# NotSoSmartWatch-BASIC-BOTTOM-version2.net
KiCad netlist of a schematic drawn in EAGLE
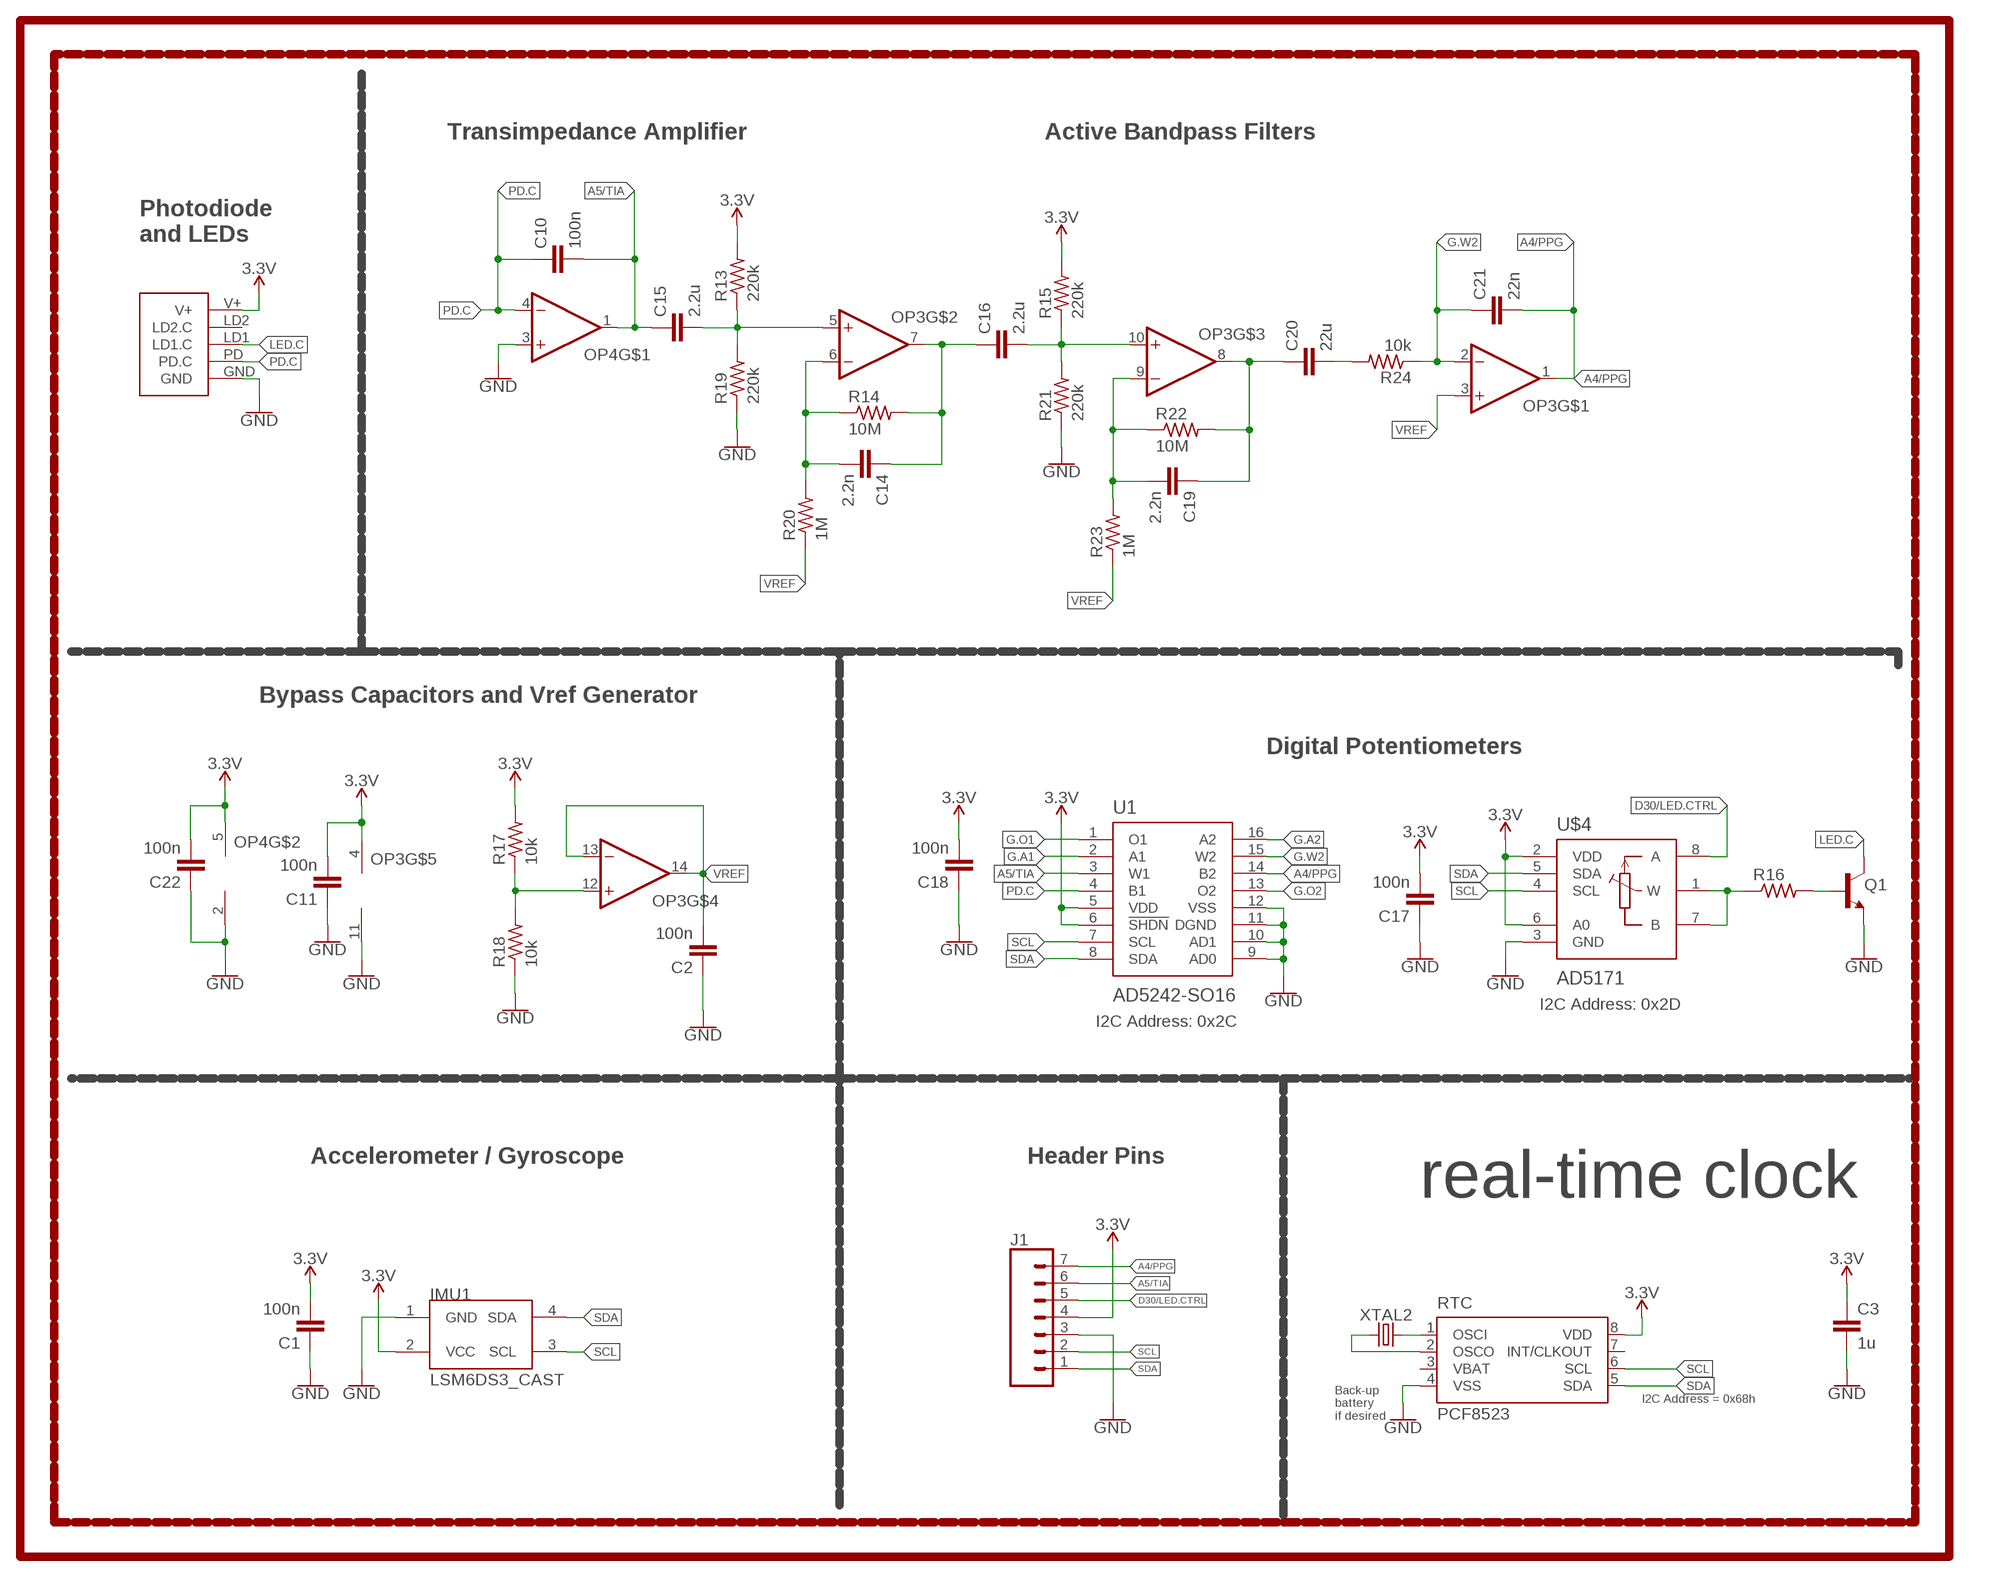
[diagram p0: schematic, sheet 1]

(export (version "E")
  (design (tool "Eeschema 10.0.6"))
  (components
    (comp (ref "C1")
      (value "100n")
      (footprint "eagle-import:C0603")
      (libsource (lib "eagle-import") (part "CAPACITOR0603"))
    )
    (comp (ref "C2")
      (value "100n")
      (footprint "eagle-import:C0603")
      (libsource (lib "eagle-import") (part "CAPACITOR0603"))
    )
    (comp (ref "C3")
      (value "1u")
      (footprint "eagle-import:C0603")
      (libsource (lib "eagle-import") (part "CAPACITOR0603"))
    )
    (comp (ref "C10")
      (value "100n")
      (footprint "eagle-import:C0603")
      (libsource (lib "eagle-import") (part "CAPACITOR0603"))
    )
    (comp (ref "C11")
      (value "100n")
      (footprint "eagle-import:C0603")
      (libsource (lib "eagle-import") (part "CAPACITOR0603"))
    )
    (comp (ref "C14")
      (value "2.2n")
      (footprint "eagle-import:C0603")
      (libsource (lib "eagle-import") (part "CAPACITOR0603"))
    )
    (comp (ref "C15")
      (value "2.2u")
      (footprint "eagle-import:C0603")
      (libsource (lib "eagle-import") (part "CAPACITOR0603"))
    )
    (comp (ref "C16")
      (value "2.2u")
      (footprint "eagle-import:C0603")
      (libsource (lib "eagle-import") (part "CAPACITOR0603"))
    )
    (comp (ref "C17")
      (value "100n")
      (footprint "eagle-import:C0603")
      (libsource (lib "eagle-import") (part "CAPACITOR0603"))
    )
    (comp (ref "C18")
      (value "100n")
      (footprint "eagle-import:C0603")
      (libsource (lib "eagle-import") (part "CAPACITOR0603"))
    )
    (comp (ref "C19")
      (value "2.2n")
      (footprint "eagle-import:C0603")
      (libsource (lib "eagle-import") (part "CAPACITOR0603"))
    )
    (comp (ref "C20")
      (value "22u")
      (footprint "eagle-import:C0603")
      (libsource (lib "eagle-import") (part "CAPACITOR0603"))
    )
    (comp (ref "C21")
      (value "22n")
      (footprint "eagle-import:C0603")
      (libsource (lib "eagle-import") (part "CAPACITOR0603"))
    )
    (comp (ref "C22")
      (value "100n")
      (footprint "eagle-import:C0603")
      (libsource (lib "eagle-import") (part "CAPACITOR0603"))
    )
    (comp (ref "IMU1")
      (value "LSM6DS3_CAST")
      (footprint "eagle-import:LSM6DS3_CAST")
      (libsource (lib "eagle-import") (part "LSM6DS3_CAST"))
    )
    (comp (ref "J1")
      (value "CONN_07-1.27MM")
      (footprint "eagle-import:1X07_1.27MM")
      (libsource (lib "eagle-import") (part "CONN_07-1.27MM"))
    )
    (comp (ref "OP3")
      (value "OP-QUAD-SO14")
      (footprint "eagle-import:SO14")
      (libsource (lib "eagle-import") (part "OP-QUAD-SO14"))
    )
    (comp (ref "OP4")
      (value "OP-SINGLEOT")
      (footprint "eagle-import:SOT23-5")
      (libsource (lib "eagle-import") (part "OP-SINGLEOT"))
    )
    (comp (ref "Q1")
      (value "NPN-GENERIC")
      (footprint "eagle-import:SOT23-3")
      (libsource (lib "eagle-import") (part "NPN-GENERIC"))
    )
    (comp (ref "R13")
      (value "220k")
      (footprint "eagle-import:R0603")
      (libsource (lib "eagle-import") (part "RESISTOR0603"))
    )
    (comp (ref "R14")
      (value "10M")
      (footprint "eagle-import:R0603")
      (libsource (lib "eagle-import") (part "RESISTOR0603"))
    )
    (comp (ref "R15")
      (value "220k")
      (footprint "eagle-import:R0603")
      (libsource (lib "eagle-import") (part "RESISTOR0603"))
    )
    (comp (ref "R16")
      (value "RESISTOR0603")
      (footprint "eagle-import:R0603")
      (libsource (lib "eagle-import") (part "RESISTOR0603"))
    )
    (comp (ref "R17")
      (value "10k")
      (footprint "eagle-import:R0402")
      (libsource (lib "eagle-import") (part "RESISTOR0402"))
    )
    (comp (ref "R18")
      (value "10k")
      (footprint "eagle-import:R0402")
      (libsource (lib "eagle-import") (part "RESISTOR0402"))
    )
    (comp (ref "R19")
      (value "220k")
      (footprint "eagle-import:R0603")
      (libsource (lib "eagle-import") (part "RESISTOR0603"))
    )
    (comp (ref "R20")
      (value "1M")
      (footprint "eagle-import:R0603")
      (libsource (lib "eagle-import") (part "RESISTOR0603"))
    )
    (comp (ref "R21")
      (value "220k")
      (footprint "eagle-import:R0603")
      (libsource (lib "eagle-import") (part "RESISTOR0603"))
    )
    (comp (ref "R22")
      (value "10M")
      (footprint "eagle-import:R0603")
      (libsource (lib "eagle-import") (part "RESISTOR0603"))
    )
    (comp (ref "R23")
      (value "1M")
      (footprint "eagle-import:R0603")
      (libsource (lib "eagle-import") (part "RESISTOR0603"))
    )
    (comp (ref "R24")
      (value "10k")
      (footprint "eagle-import:R0603")
      (libsource (lib "eagle-import") (part "RESISTOR0603"))
    )
    (comp (ref "RTC")
      (value "PCF8523")
      (footprint "eagle-import:SO8")
      (libsource (lib "eagle-import") (part "PCF8523"))
    )
    (comp (ref "U$3")
      (value "PPG.MODULE.2")
      (footprint "eagle-import:PPG.MODULE.2")
      (libsource (lib "eagle-import") (part "PPG.MODULE.2"))
    )
    (comp (ref "U$4")
      (value "AD5171")
      (footprint "eagle-import:SOT-23-8")
      (libsource (lib "eagle-import") (part "AD5171"))
    )
    (comp (ref "U1")
      (value "AD5242-SO16")
      (footprint "eagle-import:SO16")
      (libsource (lib "eagle-import") (part "AD5242-SO16"))
    )
    (comp (ref "XTAL2")
      (value "32.7680kHz")
      (footprint "eagle-import:2-SMD.NOLEAD.2.0MMTO1.2MM")
      (fields (field (name "FREQ") "32.7680KHZ"))
      (libsource (lib "eagle-import") (part "CRYSTALECS-.327-12.5-12-C-TR"))
    )
  )
  (nets
    (net (code "1") (name "/VBAT") (class "Default")
      (node (ref "RTC") (pin "3") (pinfunction "VBAT_3") (pintype "power_in"))
    )
    (net (code "2") (name "3.3V") (class "Default")
      (node (ref "C1") (pin "2") (pinfunction "2_2") (pintype "passive"))
      (node (ref "C11") (pin "2") (pinfunction "2_2") (pintype "passive"))
      (node (ref "C17") (pin "2") (pinfunction "2_2") (pintype "passive"))
      (node (ref "C18") (pin "2") (pinfunction "2_2") (pintype "passive"))
      (node (ref "C22") (pin "2") (pinfunction "2_2") (pintype "passive"))
      (node (ref "C3") (pin "1") (pinfunction "1_1") (pintype "passive"))
      (node (ref "IMU1") (pin "2") (pinfunction "VCC_2") (pintype "bidirectional"))
      (node (ref "J1") (pin "4") (pinfunction "4_4") (pintype "passive"))
      (node (ref "OP3") (pin "4") (pinfunction "V+_4") (pintype "power_in"))
      (node (ref "OP4") (pin "5") (pinfunction "V+_5") (pintype "power_in"))
      (node (ref "R13") (pin "2") (pinfunction "2_2") (pintype "passive"))
      (node (ref "R15") (pin "2") (pinfunction "2_2") (pintype "passive"))
      (node (ref "R17") (pin "2") (pinfunction "2_2") (pintype "passive"))
      (node (ref "RTC") (pin "8") (pinfunction "VDD_8") (pintype "power_in"))
      (node (ref "U$3") (pin "V+") (pinfunction "V+_V+") (pintype "bidirectional"))
      (node (ref "U$4") (pin "2") (pinfunction "VDD_2") (pintype "bidirectional"))
      (node (ref "U$4") (pin "6") (pinfunction "A0_6") (pintype "bidirectional"))
      (node (ref "U1") (pin "5") (pinfunction "VDD_5") (pintype "bidirectional"))
      (node (ref "U1") (pin "6") (pinfunction "~{SHDN}_6") (pintype "bidirectional"))
    )
    (net (code "3") (name "A4{slash}PPG") (class "Default")
      (node (ref "C21") (pin "2") (pinfunction "2_2") (pintype "passive"))
      (node (ref "J1") (pin "7") (pinfunction "7_7") (pintype "passive"))
      (node (ref "OP3") (pin "1") (pinfunction "OUT_1") (pintype "output"))
      (node (ref "U1") (pin "14") (pinfunction "B2_14") (pintype "bidirectional"))
    )
    (net (code "4") (name "A5{slash}TIA") (class "Default")
      (node (ref "C10") (pin "2") (pinfunction "2_2") (pintype "passive"))
      (node (ref "C15") (pin "1") (pinfunction "1_1") (pintype "passive"))
      (node (ref "J1") (pin "6") (pinfunction "6_6") (pintype "passive"))
      (node (ref "OP4") (pin "1") (pinfunction "OUT_1") (pintype "output"))
      (node (ref "U1") (pin "3") (pinfunction "W1_3") (pintype "bidirectional"))
    )
    (net (code "5") (name "D30{slash}LED.CTRL") (class "Default")
      (node (ref "J1") (pin "5") (pinfunction "5_5") (pintype "passive"))
      (node (ref "U$4") (pin "8") (pinfunction "A_8") (pintype "bidirectional"))
    )
    (net (code "6") (name "G.A1") (class "Default")
      (node (ref "U1") (pin "2") (pinfunction "A1_2") (pintype "bidirectional"))
    )
    (net (code "7") (name "G.A2") (class "Default")
      (node (ref "U1") (pin "16") (pinfunction "A2_16") (pintype "bidirectional"))
    )
    (net (code "8") (name "G.O1") (class "Default")
      (node (ref "U1") (pin "1") (pinfunction "O1_1") (pintype "bidirectional"))
    )
    (net (code "9") (name "G.O2") (class "Default")
      (node (ref "U1") (pin "13") (pinfunction "O2_13") (pintype "bidirectional"))
    )
    (net (code "10") (name "G.W2") (class "Default")
      (node (ref "C21") (pin "1") (pinfunction "1_1") (pintype "passive"))
      (node (ref "OP3") (pin "2") (pinfunction "-IN_2") (pintype "input"))
      (node (ref "R24") (pin "1") (pinfunction "1_1") (pintype "passive"))
      (node (ref "U1") (pin "15") (pinfunction "W2_15") (pintype "bidirectional"))
    )
    (net (code "11") (name "GND") (class "Default")
      (node (ref "C1") (pin "1") (pinfunction "1_1") (pintype "passive"))
      (node (ref "C11") (pin "1") (pinfunction "1_1") (pintype "passive"))
      (node (ref "C17") (pin "1") (pinfunction "1_1") (pintype "passive"))
      (node (ref "C18") (pin "1") (pinfunction "1_1") (pintype "passive"))
      (node (ref "C2") (pin "1") (pinfunction "1_1") (pintype "passive"))
      (node (ref "C22") (pin "1") (pinfunction "1_1") (pintype "passive"))
      (node (ref "C3") (pin "2") (pinfunction "2_2") (pintype "passive"))
      (node (ref "IMU1") (pin "1") (pinfunction "GND_1") (pintype "bidirectional"))
      (node (ref "J1") (pin "3") (pinfunction "3_3") (pintype "passive"))
      (node (ref "OP3") (pin "11") (pinfunction "V-_11") (pintype "power_in"))
      (node (ref "OP4") (pin "2") (pinfunction "V-_2") (pintype "power_in"))
      (node (ref "OP4") (pin "3") (pinfunction "+IN_3") (pintype "input"))
      (node (ref "Q1") (pin "2") (pinfunction "E_2") (pintype "passive"))
      (node (ref "R18") (pin "1") (pinfunction "1_1") (pintype "passive"))
      (node (ref "R19") (pin "1") (pinfunction "1_1") (pintype "passive"))
      (node (ref "R21") (pin "1") (pinfunction "1_1") (pintype "passive"))
      (node (ref "RTC") (pin "4") (pinfunction "VSS_4") (pintype "power_in"))
      (node (ref "U$3") (pin "GND") (pinfunction "GND_GND") (pintype "bidirectional"))
      (node (ref "U$4") (pin "3") (pinfunction "GND_3") (pintype "bidirectional"))
      (node (ref "U1") (pin "10") (pinfunction "AD1_10") (pintype "bidirectional"))
      (node (ref "U1") (pin "11") (pinfunction "DGND_11") (pintype "bidirectional"))
      (node (ref "U1") (pin "12") (pinfunction "VSS_12") (pintype "bidirectional"))
      (node (ref "U1") (pin "9") (pinfunction "AD0_9") (pintype "bidirectional"))
    )
    (net (code "12") (name "LED.C") (class "Default")
      (node (ref "Q1") (pin "3") (pinfunction "C_3") (pintype "passive"))
      (node (ref "U$3") (pin "LD1") (pinfunction "LD1.C_LD1") (pintype "bidirectional"))
    )
    (net (code "13") (name "Net-(C20-Pad2)") (class "Default")
      (node (ref "C20") (pin "2") (pinfunction "2_2") (pintype "passive"))
      (node (ref "R24") (pin "2") (pinfunction "2_2") (pintype "passive"))
    )
    (net (code "14") (name "Net-(OP3B-+IN)") (class "Default")
      (node (ref "C15") (pin "2") (pinfunction "2_2") (pintype "passive"))
      (node (ref "OP3") (pin "5") (pinfunction "+IN_5") (pintype "input"))
      (node (ref "R13") (pin "1") (pinfunction "1_1") (pintype "passive"))
      (node (ref "R19") (pin "2") (pinfunction "2_2") (pintype "passive"))
    )
    (net (code "15") (name "Net-(OP3B--IN)") (class "Default")
      (node (ref "C14") (pin "2") (pinfunction "2_2") (pintype "passive"))
      (node (ref "OP3") (pin "6") (pinfunction "-IN_6") (pintype "input"))
      (node (ref "R14") (pin "1") (pinfunction "1_1") (pintype "passive"))
      (node (ref "R20") (pin "2") (pinfunction "2_2") (pintype "passive"))
    )
    (net (code "16") (name "Net-(OP3B-OUT)") (class "Default")
      (node (ref "C14") (pin "1") (pinfunction "1_1") (pintype "passive"))
      (node (ref "C16") (pin "1") (pinfunction "1_1") (pintype "passive"))
      (node (ref "OP3") (pin "7") (pinfunction "OUT_7") (pintype "output"))
      (node (ref "R14") (pin "2") (pinfunction "2_2") (pintype "passive"))
    )
    (net (code "17") (name "Net-(OP3C-+IN)") (class "Default")
      (node (ref "C16") (pin "2") (pinfunction "2_2") (pintype "passive"))
      (node (ref "OP3") (pin "10") (pinfunction "+IN_10") (pintype "input"))
      (node (ref "R15") (pin "1") (pinfunction "1_1") (pintype "passive"))
      (node (ref "R21") (pin "2") (pinfunction "2_2") (pintype "passive"))
    )
    (net (code "18") (name "Net-(OP3C--IN)") (class "Default")
      (node (ref "C19") (pin "2") (pinfunction "2_2") (pintype "passive"))
      (node (ref "OP3") (pin "9") (pinfunction "-IN_9") (pintype "input"))
      (node (ref "R22") (pin "1") (pinfunction "1_1") (pintype "passive"))
      (node (ref "R23") (pin "2") (pinfunction "2_2") (pintype "passive"))
    )
    (net (code "19") (name "Net-(OP3C-OUT)") (class "Default")
      (node (ref "C19") (pin "1") (pinfunction "1_1") (pintype "passive"))
      (node (ref "C20") (pin "1") (pinfunction "1_1") (pintype "passive"))
      (node (ref "OP3") (pin "8") (pinfunction "OUT_8") (pintype "output"))
      (node (ref "R22") (pin "2") (pinfunction "2_2") (pintype "passive"))
    )
    (net (code "20") (name "Net-(OP3D-+IN)") (class "Default")
      (node (ref "OP3") (pin "12") (pinfunction "+IN_12") (pintype "input"))
      (node (ref "R17") (pin "1") (pinfunction "1_1") (pintype "passive"))
      (node (ref "R18") (pin "2") (pinfunction "2_2") (pintype "passive"))
    )
    (net (code "21") (name "Net-(Q1-B)") (class "Default")
      (node (ref "Q1") (pin "1") (pinfunction "B_1") (pintype "passive"))
      (node (ref "R16") (pin "2") (pinfunction "2_2") (pintype "passive"))
    )
    (net (code "22") (name "Net-(RTC-OSCI)") (class "Default")
      (node (ref "RTC") (pin "1") (pinfunction "OSCI_1") (pintype "bidirectional"))
      (node (ref "XTAL2") (pin "P$2") (pinfunction "2_P$2") (pintype "passive"))
    )
    (net (code "23") (name "Net-(RTC-OSCO)") (class "Default")
      (node (ref "RTC") (pin "2") (pinfunction "OSCO_2") (pintype "bidirectional"))
      (node (ref "XTAL2") (pin "P$1") (pinfunction "1_P$1") (pintype "passive"))
    )
    (net (code "24") (name "Net-(U$4-B)") (class "Default")
      (node (ref "R16") (pin "1") (pinfunction "1_1") (pintype "passive"))
      (node (ref "U$4") (pin "1") (pinfunction "W_1") (pintype "bidirectional"))
      (node (ref "U$4") (pin "7") (pinfunction "B_7") (pintype "bidirectional"))
    )
    (net (code "25") (name "PD.C") (class "Default")
      (node (ref "C10") (pin "1") (pinfunction "1_1") (pintype "passive"))
      (node (ref "OP4") (pin "4") (pinfunction "-IN_4") (pintype "input"))
      (node (ref "U$3") (pin "PD") (pinfunction "PD.C_PD") (pintype "bidirectional"))
      (node (ref "U1") (pin "4") (pinfunction "B1_4") (pintype "bidirectional"))
    )
    (net (code "26") (name "SCL") (class "Default")
      (node (ref "IMU1") (pin "3") (pinfunction "SCL_3") (pintype "bidirectional"))
      (node (ref "J1") (pin "2") (pinfunction "2_2") (pintype "passive"))
      (node (ref "RTC") (pin "6") (pinfunction "SCL_6") (pintype "bidirectional"))
      (node (ref "U$4") (pin "4") (pinfunction "SCL_4") (pintype "bidirectional"))
      (node (ref "U1") (pin "7") (pinfunction "SCL_7") (pintype "bidirectional"))
    )
    (net (code "27") (name "SDA") (class "Default")
      (node (ref "IMU1") (pin "4") (pinfunction "SDA_4") (pintype "bidirectional"))
      (node (ref "J1") (pin "1") (pinfunction "1_1") (pintype "passive"))
      (node (ref "RTC") (pin "5") (pinfunction "SDA_5") (pintype "bidirectional"))
      (node (ref "U$4") (pin "5") (pinfunction "SDA_5") (pintype "bidirectional"))
      (node (ref "U1") (pin "8") (pinfunction "SDA_8") (pintype "bidirectional"))
    )
    (net (code "28") (name "VREF") (class "Default")
      (node (ref "C2") (pin "2") (pinfunction "2_2") (pintype "passive"))
      (node (ref "OP3") (pin "13") (pinfunction "-IN_13") (pintype "input"))
      (node (ref "OP3") (pin "14") (pinfunction "OUT_14") (pintype "output"))
      (node (ref "OP3") (pin "3") (pinfunction "+IN_3") (pintype "input"))
      (node (ref "R20") (pin "1") (pinfunction "1_1") (pintype "passive"))
      (node (ref "R23") (pin "1") (pinfunction "1_1") (pintype "passive"))
    )
    (net (code "29") (name "unconnected-(RTC-INT{slash}CLKOUT-Pad7)") (class "Default")
      (node (ref "RTC") (pin "7") (pinfunction "INT/CLKOUT_7") (pintype "bidirectional"))
    )
    (net (code "30") (name "unconnected-(U$3-LD2.C-PadLD2)") (class "Default")
      (node (ref "U$3") (pin "LD2") (pinfunction "LD2.C_LD2") (pintype "bidirectional"))
    )
  )
)
